# USB.net
KiCad netlist of a schematic drawn in Altium Designer
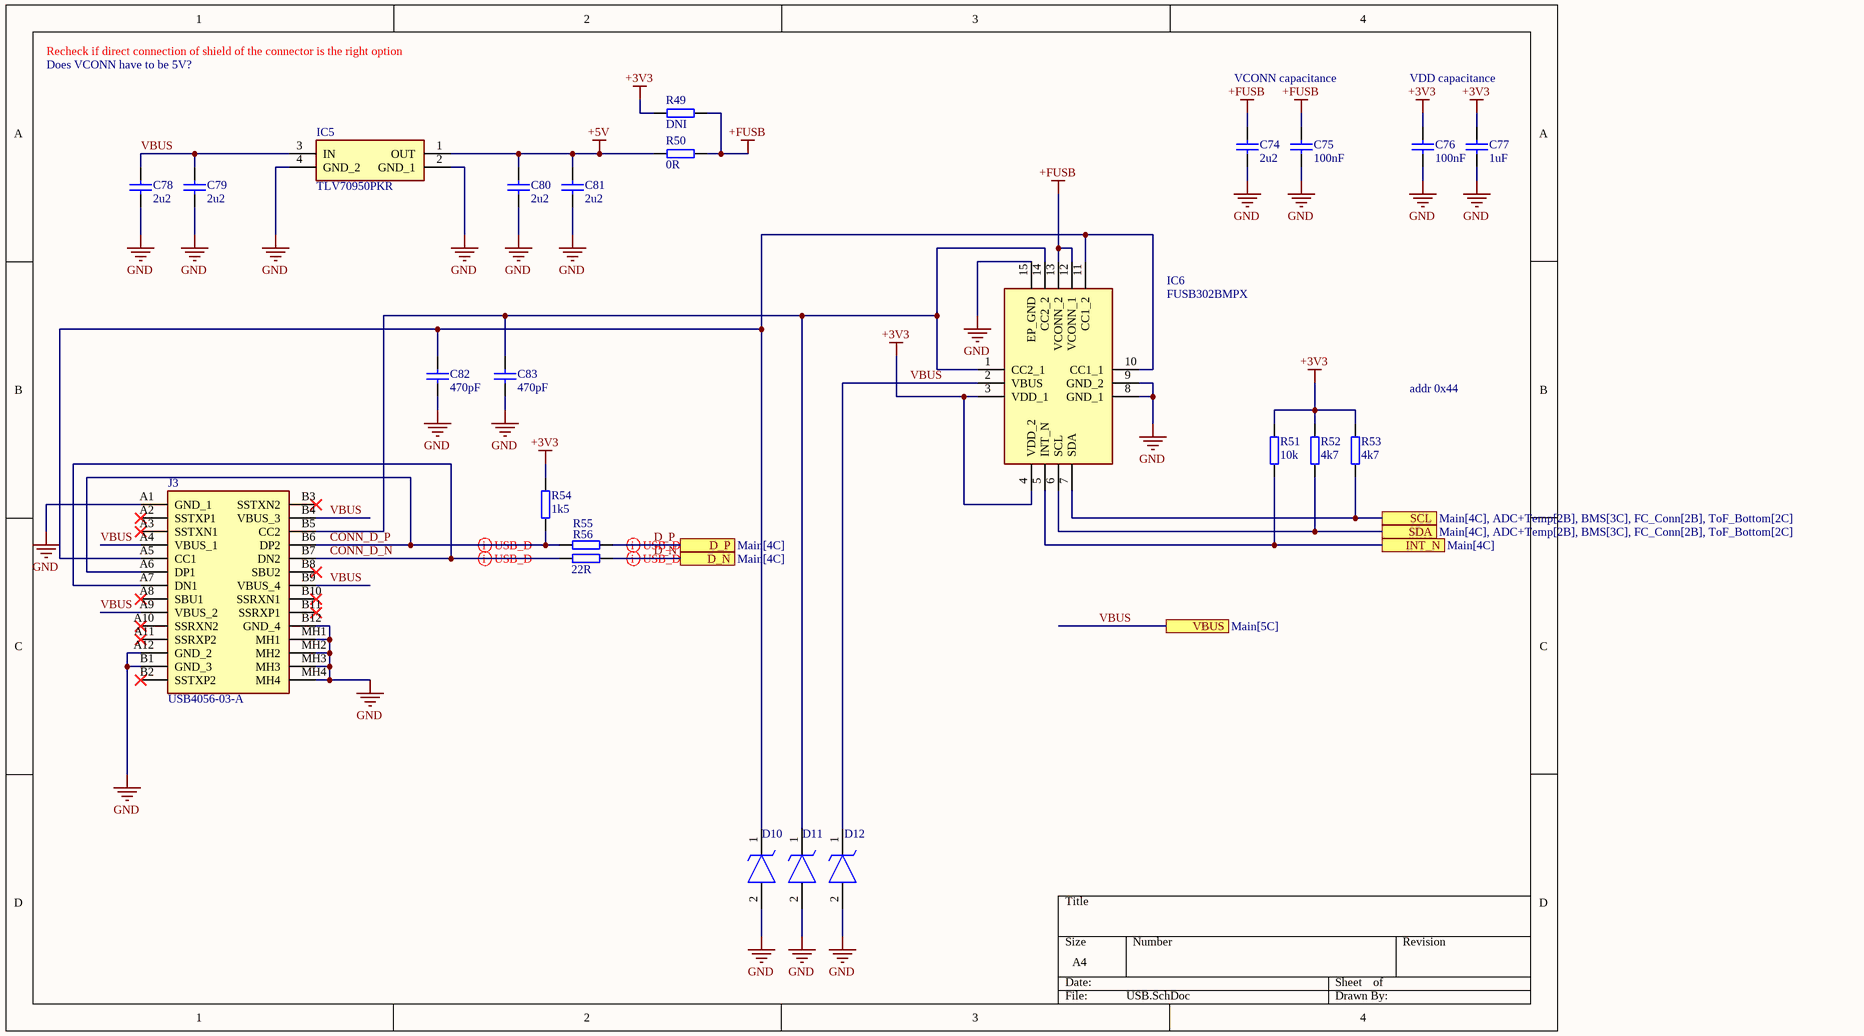
[diagram p0: USB.SchDoc]

(export (version "E")
  (design (tool "Eeschema 10.0.6"))
  (components
    (comp (ref "C74")
      (value "2u2")
      (footprint "CAP0603")
      (fields
        (field (name "VOLTAGE") "50V")
        (field (name "MANUFACTURER_PART_NUMBER") "GRT188R61H225KE13D")
        (field (name "Comment") "Cap0603")
      )
      (libsource (lib "capacitorsSMD") (part "Cap0603"))
    )
    (comp (ref "C75")
      (value "100nF")
      (footprint "CAP0402")
      (fields
        (field (name "VOLTAGE") "50V")
        (field (name "MANUFACTURER_PART_NUMBER") "GRM155R71H104ME14D")
        (field (name "Comment") "Cap0402")
      )
      (libsource (lib "capacitorsSMD") (part "Cap0402"))
    )
    (comp (ref "C76")
      (value "100nF")
      (footprint "CAP0402")
      (fields
        (field (name "VOLTAGE") "50V")
        (field (name "MANUFACTURER_PART_NUMBER") "GRM155R71H104ME14D")
        (field (name "Comment") "Cap0402")
      )
      (libsource (lib "capacitorsSMD") (part "Cap0402"))
    )
    (comp (ref "C77")
      (value "1uF")
      (footprint "CAP0402")
      (fields
        (field (name "VOLTAGE") "50V")
        (field (name "MANUFACTURER_PART_NUMBER") "GRM155R61H105KE05J")
        (field (name "Comment") "Cap0402")
      )
      (libsource (lib "capacitorsSMD") (part "Cap0402"))
    )
    (comp (ref "C78")
      (value "2u2")
      (footprint "CAP0603")
      (fields
        (field (name "VOLTAGE") "50V")
        (field (name "MANUFACTURER_PART_NUMBER") "GRT188R61H225KE13D")
        (field (name "Comment") "Cap0603")
      )
      (libsource (lib "capacitorsSMD") (part "Cap0603"))
    )
    (comp (ref "C79")
      (value "2u2")
      (footprint "CAP0603")
      (fields
        (field (name "VOLTAGE") "50V")
        (field (name "MANUFACTURER_PART_NUMBER") "GRT188R61H225KE13D")
        (field (name "Comment") "Cap0603")
      )
      (libsource (lib "capacitorsSMD") (part "Cap0603"))
    )
    (comp (ref "C80")
      (value "2u2")
      (footprint "CAP0603")
      (fields
        (field (name "VOLTAGE") "50V")
        (field (name "MANUFACTURER_PART_NUMBER") "GRT188R61H225KE13D")
        (field (name "Comment") "Cap0603")
      )
      (libsource (lib "capacitorsSMD") (part "Cap0603"))
    )
    (comp (ref "C81")
      (value "2u2")
      (footprint "CAP0603")
      (fields
        (field (name "VOLTAGE") "50V")
        (field (name "MANUFACTURER_PART_NUMBER") "GRT188R61H225KE13D")
        (field (name "Comment") "Cap0603")
      )
      (libsource (lib "capacitorsSMD") (part "Cap0603"))
    )
    (comp (ref "C82")
      (value "470pF")
      (footprint "CAP0402")
      (fields
        (field (name "VOLTAGE") "50V")
        (field (name "MANUFACTURER_PART_NUMBER") "GCM155R71H471MA37D")
        (field (name "Comment") "Cap0402")
      )
      (libsource (lib "capacitorsSMD") (part "Cap0402"))
    )
    (comp (ref "C83")
      (value "470pF")
      (footprint "CAP0402")
      (fields
        (field (name "VOLTAGE") "50V")
        (field (name "MANUFACTURER_PART_NUMBER") "GCM155R71H471MA37D")
        (field (name "Comment") "Cap0402")
      )
      (libsource (lib "capacitorsSMD") (part "Cap0402"))
    )
    (comp (ref "D10")
      (value "D1213A-01LP4-7B")
      (footprint "SamacSys:D1213A01LP47B")
      (description "TVS Diode (Uni-directional)")
      (fields (field (name "MOUSER PART NUMBER") "621-D1213A-01LP4-7B"))
      (libsource (lib "*") (part "D1213A-01LP4-7B"))
    )
    (comp (ref "D11")
      (value "D1213A-01LP4-7B")
      (footprint "SamacSys:D1213A01LP47B")
      (description "TVS Diode (Uni-directional)")
      (fields (field (name "MOUSER PART NUMBER") "621-D1213A-01LP4-7B"))
      (libsource (lib "*") (part "D1213A-01LP4-7B"))
    )
    (comp (ref "D12")
      (value "DF2S24FS,L3M")
      (footprint "SamacSys:SODFL1006X45N")
      (description "TVS Diode (Uni-directional)")
      (fields (field (name "MOUSER PART NUMBER") "757-DF2S24FSL3M"))
      (libsource (lib "*") (part "DF2S24FS,L3M"))
    )
    (comp (ref "IC5")
      (value "TLV70950PKR")
      (footprint "SamacSys:TL431AQPKG3")
      (description "Integrated Circuit")
      (fields (field (name "MOUSER PART NUMBER") "595-TLV70950PKR"))
      (libsource (lib "*") (part "TLV70950PKR"))
    )
    (comp (ref "IC6")
      (value "FUSB302BMPX")
      (footprint "SamacSys:QFN50P250X250X80-15N")
      (description "Integrated Circuit")
      (fields (field (name "MOUSER PART NUMBER") "512-FUSB302BMPX"))
      (libsource (lib "*") (part "FUSB302BMPX"))
    )
    (comp (ref "J3")
      (value "USB4056-03-A")
      (footprint "SamacSys:USB405603A")
      (description "Connector")
      (fields (field (name "MOUSER PART NUMBER") "640-USB4056-03-A"))
      (libsource (lib "*") (part "USB4056-03-A"))
    )
    (comp (ref "R49")
      (value "DNI")
      (footprint "RES0402")
      (fields (field (name "Comment") "Res0402"))
      (libsource (lib "resistorSMD") (part "Res0402"))
    )
    (comp (ref "R50")
      (value "0R")
      (footprint "RES0402")
      (fields (field (name "MANUFACTURER_PART_NUMBER") "RCA04020000ZSED") (field (name "Comment") "Res0402"))
      (libsource (lib "resistorSMD") (part "Res0402"))
    )
    (comp (ref "R51")
      (value "10k")
      (footprint "RES0402")
      (fields (field (name "MANUFACTURER_PART_NUMBER") "ERA-2AED103X") (field (name "Comment") "Res0402"))
      (libsource (lib "resistorSMD") (part "Res0402"))
    )
    (comp (ref "R52")
      (value "4k7")
      (footprint "RES0402")
      (fields (field (name "MANUFACTURER_PART_NUMBER") "RC0402JR-7W4K7L") (field (name "Comment") "Res0402"))
      (libsource (lib "resistorSMD") (part "Res0402"))
    )
    (comp (ref "R53")
      (value "4k7")
      (footprint "RES0402")
      (fields (field (name "MANUFACTURER_PART_NUMBER") "RC0402JR-7W4K7L") (field (name "Comment") "Res0402"))
      (libsource (lib "resistorSMD") (part "Res0402"))
    )
    (comp (ref "R54")
      (value "1k5")
      (footprint "RES0402")
      (fields (field (name "MANUFACTURER_PART_NUMBER") "ERA-2AEB152X") (field (name "Comment") "Res0402"))
      (libsource (lib "resistorSMD") (part "Res0402"))
    )
    (comp (ref "R55")
      (value "Res0402")
      (footprint "RES0402")
      (fields (field (name "MANUFACTURER_PART_NUMBER") "MCS04020C2209FE000"))
      (libsource (lib "resistorSMD") (part "Res0402"))
    )
    (comp (ref "R56")
      (value "22R")
      (footprint "RES0402")
      (fields
        (field (name "MANUFACTURER_PART_NUMBER") "MCS04020C2209FE000")
        (field (name "Comment") "Res0402")
      )
      (libsource (lib "resistorSMD") (part "Res0402"))
    )
  )
  (nets
    (net (code "1") (name "+3V3") (class "Default")
      (node (ref "C76") (pin "2") (pinfunction "2_2") (pintype "passive"))
      (node (ref "C77") (pin "2") (pinfunction "2_2") (pintype "passive"))
      (node (ref "IC6") (pin "3") (pinfunction "VDD_1_3") (pintype "passive"))
      (node (ref "IC6") (pin "4") (pinfunction "VDD_2_4") (pintype "passive"))
      (node (ref "R49") (pin "2") (pinfunction "2_2") (pintype "passive"))
      (node (ref "R51") (pin "2") (pinfunction "2_2") (pintype "passive"))
      (node (ref "R52") (pin "2") (pinfunction "2_2") (pintype "passive"))
      (node (ref "R53") (pin "2") (pinfunction "2_2") (pintype "passive"))
      (node (ref "R54") (pin "2") (pinfunction "2_2") (pintype "passive"))
    )
    (net (code "2") (name "+5V") (class "Default")
      (node (ref "C80") (pin "2") (pinfunction "2_2") (pintype "passive"))
      (node (ref "C81") (pin "2") (pinfunction "2_2") (pintype "passive"))
      (node (ref "IC5") (pin "1") (pinfunction "OUT_1") (pintype "passive"))
      (node (ref "R50") (pin "2") (pinfunction "2_2") (pintype "passive"))
    )
    (net (code "3") (name "+FUSB") (class "Default")
      (node (ref "C74") (pin "2") (pinfunction "2_2") (pintype "passive"))
      (node (ref "C75") (pin "2") (pinfunction "2_2") (pintype "passive"))
      (node (ref "IC6") (pin "12") (pinfunction "VCONN_1_12") (pintype "passive"))
      (node (ref "IC6") (pin "13") (pinfunction "VCONN_2_13") (pintype "passive"))
      (node (ref "R49") (pin "1") (pinfunction "1_1") (pintype "passive"))
      (node (ref "R50") (pin "1") (pinfunction "1_1") (pintype "passive"))
    )
    (net (code "4") (name "/CONN_D_N") (class "Default")
      (node (ref "J3") (pin "A7") (pinfunction "DN1_A7") (pintype "passive"))
      (node (ref "J3") (pin "B7") (pinfunction "DN2_B7") (pintype "passive"))
      (node (ref "R56") (pin "1") (pinfunction "1_1") (pintype "passive"))
    )
    (net (code "5") (name "/CONN_D_P") (class "Default")
      (node (ref "J3") (pin "A6") (pinfunction "DP1_A6") (pintype "passive"))
      (node (ref "J3") (pin "B6") (pinfunction "DP2_B6") (pintype "passive"))
      (node (ref "R54") (pin "1") (pinfunction "1_1") (pintype "passive"))
      (node (ref "R55") (pin "1") (pinfunction "1_1") (pintype "passive"))
    )
    (net (code "6") (name "/D_N") (class "Default")
      (node (ref "R56") (pin "2") (pinfunction "2_2") (pintype "passive"))
    )
    (net (code "7") (name "/D_P") (class "Default")
      (node (ref "R55") (pin "2") (pinfunction "2_2") (pintype "passive"))
    )
    (net (code "8") (name "/INT_N") (class "Default")
      (node (ref "IC6") (pin "5") (pinfunction "INT_N_5") (pintype "passive"))
      (node (ref "R51") (pin "1") (pinfunction "1_1") (pintype "passive"))
    )
    (net (code "9") (name "/SCL") (class "Default")
      (node (ref "IC6") (pin "7") (pinfunction "SDA_7") (pintype "passive"))
      (node (ref "R53") (pin "1") (pinfunction "1_1") (pintype "passive"))
    )
    (net (code "10") (name "/SDA") (class "Default")
      (node (ref "IC6") (pin "6") (pinfunction "SCL_6") (pintype "passive"))
      (node (ref "R52") (pin "1") (pinfunction "1_1") (pintype "passive"))
    )
    (net (code "11") (name "/VBUS") (class "Default")
      (node (ref "C78") (pin "2") (pinfunction "2_2") (pintype "passive"))
      (node (ref "C79") (pin "2") (pinfunction "2_2") (pintype "passive"))
      (node (ref "D12") (pin "1") (pinfunction "K_1") (pintype "passive"))
      (node (ref "IC5") (pin "3") (pinfunction "IN_3") (pintype "passive"))
      (node (ref "IC6") (pin "2") (pinfunction "VBUS_2") (pintype "passive"))
      (node (ref "J3") (pin "A4") (pinfunction "VBUS_1_A4") (pintype "passive"))
      (node (ref "J3") (pin "A9") (pinfunction "VBUS_2_A9") (pintype "passive"))
      (node (ref "J3") (pin "B4") (pinfunction "VBUS_3_B4") (pintype "passive"))
      (node (ref "J3") (pin "B9") (pinfunction "VBUS_4_B9") (pintype "passive"))
    )
    (net (code "12") (name "GND") (class "Default")
      (node (ref "C74") (pin "1") (pinfunction "1_1") (pintype "passive"))
      (node (ref "C75") (pin "1") (pinfunction "1_1") (pintype "passive"))
      (node (ref "C76") (pin "1") (pinfunction "1_1") (pintype "passive"))
      (node (ref "C77") (pin "1") (pinfunction "1_1") (pintype "passive"))
      (node (ref "C78") (pin "1") (pinfunction "1_1") (pintype "passive"))
      (node (ref "C79") (pin "1") (pinfunction "1_1") (pintype "passive"))
      (node (ref "C80") (pin "1") (pinfunction "1_1") (pintype "passive"))
      (node (ref "C81") (pin "1") (pinfunction "1_1") (pintype "passive"))
      (node (ref "C82") (pin "1") (pinfunction "1_1") (pintype "passive"))
      (node (ref "C83") (pin "1") (pinfunction "1_1") (pintype "passive"))
      (node (ref "D10") (pin "2") (pinfunction "A_2") (pintype "passive"))
      (node (ref "D11") (pin "2") (pinfunction "A_2") (pintype "passive"))
      (node (ref "D12") (pin "2") (pinfunction "A_2") (pintype "passive"))
      (node (ref "IC5") (pin "2") (pinfunction "GND_1_2") (pintype "passive"))
      (node (ref "IC5") (pin "4") (pinfunction "GND_2_4") (pintype "passive"))
      (node (ref "IC6") (pin "15") (pinfunction "EP_GND_15") (pintype "passive"))
      (node (ref "IC6") (pin "8") (pinfunction "GND_1_8") (pintype "passive"))
      (node (ref "IC6") (pin "9") (pinfunction "GND_2_9") (pintype "passive"))
      (node (ref "J3") (pin "A1") (pinfunction "GND_1_A1") (pintype "passive"))
      (node (ref "J3") (pin "A12") (pinfunction "GND_2_A12") (pintype "passive"))
      (node (ref "J3") (pin "B1") (pinfunction "GND_3_B1") (pintype "passive"))
      (node (ref "J3") (pin "B12") (pinfunction "GND_4_B12") (pintype "passive"))
      (node (ref "J3") (pin "MH1") (pinfunction "MH1_MH1") (pintype "passive"))
      (node (ref "J3") (pin "MH2") (pinfunction "MH2_MH2") (pintype "passive"))
      (node (ref "J3") (pin "MH3") (pinfunction "MH3_MH3") (pintype "passive"))
      (node (ref "J3") (pin "MH4") (pinfunction "MH4_MH4") (pintype "passive"))
    )
    (net (code "13") (name "Net-(D10-K)") (class "Default")
      (node (ref "C82") (pin "2") (pinfunction "2_2") (pintype "passive"))
      (node (ref "D10") (pin "1") (pinfunction "K_1") (pintype "passive"))
      (node (ref "IC6") (pin "10") (pinfunction "CC1_1_10") (pintype "passive"))
      (node (ref "IC6") (pin "11") (pinfunction "CC1_2_11") (pintype "passive"))
      (node (ref "J3") (pin "A5") (pinfunction "CC1_A5") (pintype "passive"))
    )
    (net (code "14") (name "Net-(D11-K)") (class "Default")
      (node (ref "C83") (pin "2") (pinfunction "2_2") (pintype "passive"))
      (node (ref "D11") (pin "1") (pinfunction "K_1") (pintype "passive"))
      (node (ref "IC6") (pin "1") (pinfunction "CC2_1_1") (pintype "passive"))
      (node (ref "IC6") (pin "14") (pinfunction "CC2_2_14") (pintype "passive"))
      (node (ref "J3") (pin "B5") (pinfunction "CC2_B5") (pintype "passive"))
    )
    (net (code "15") (name "unconnected-(J3-SBU1-PadA8)") (class "Default")
      (node (ref "J3") (pin "A8") (pinfunction "SBU1_A8") (pintype "passive+no_connect"))
    )
    (net (code "16") (name "unconnected-(J3-SBU2-PadB8)") (class "Default")
      (node (ref "J3") (pin "B8") (pinfunction "SBU2_B8") (pintype "passive+no_connect"))
    )
    (net (code "17") (name "unconnected-(J3-SSRXN1-PadB10)") (class "Default")
      (node (ref "J3") (pin "B10") (pinfunction "SSRXN1_B10") (pintype "passive+no_connect"))
    )
    (net (code "18") (name "unconnected-(J3-SSRXN2-PadA10)") (class "Default")
      (node (ref "J3") (pin "A10") (pinfunction "SSRXN2_A10") (pintype "passive+no_connect"))
    )
    (net (code "19") (name "unconnected-(J3-SSRXP1-PadB11)") (class "Default")
      (node (ref "J3") (pin "B11") (pinfunction "SSRXP1_B11") (pintype "passive+no_connect"))
    )
    (net (code "20") (name "unconnected-(J3-SSRXP2-PadA11)") (class "Default")
      (node (ref "J3") (pin "A11") (pinfunction "SSRXP2_A11") (pintype "passive+no_connect"))
    )
    (net (code "21") (name "unconnected-(J3-SSTXN1-PadA3)") (class "Default")
      (node (ref "J3") (pin "A3") (pinfunction "SSTXN1_A3") (pintype "passive+no_connect"))
    )
    (net (code "22") (name "unconnected-(J3-SSTXN2-PadB3)") (class "Default")
      (node (ref "J3") (pin "B3") (pinfunction "SSTXN2_B3") (pintype "passive+no_connect"))
    )
    (net (code "23") (name "unconnected-(J3-SSTXP1-PadA2)") (class "Default")
      (node (ref "J3") (pin "A2") (pinfunction "SSTXP1_A2") (pintype "passive+no_connect"))
    )
    (net (code "24") (name "unconnected-(J3-SSTXP2-PadB2)") (class "Default")
      (node (ref "J3") (pin "B2") (pinfunction "SSTXP2_B2") (pintype "passive+no_connect"))
    )
  )
)
